# water_system_module.net
KiCad netlist of a schematic drawn in Altium Designer
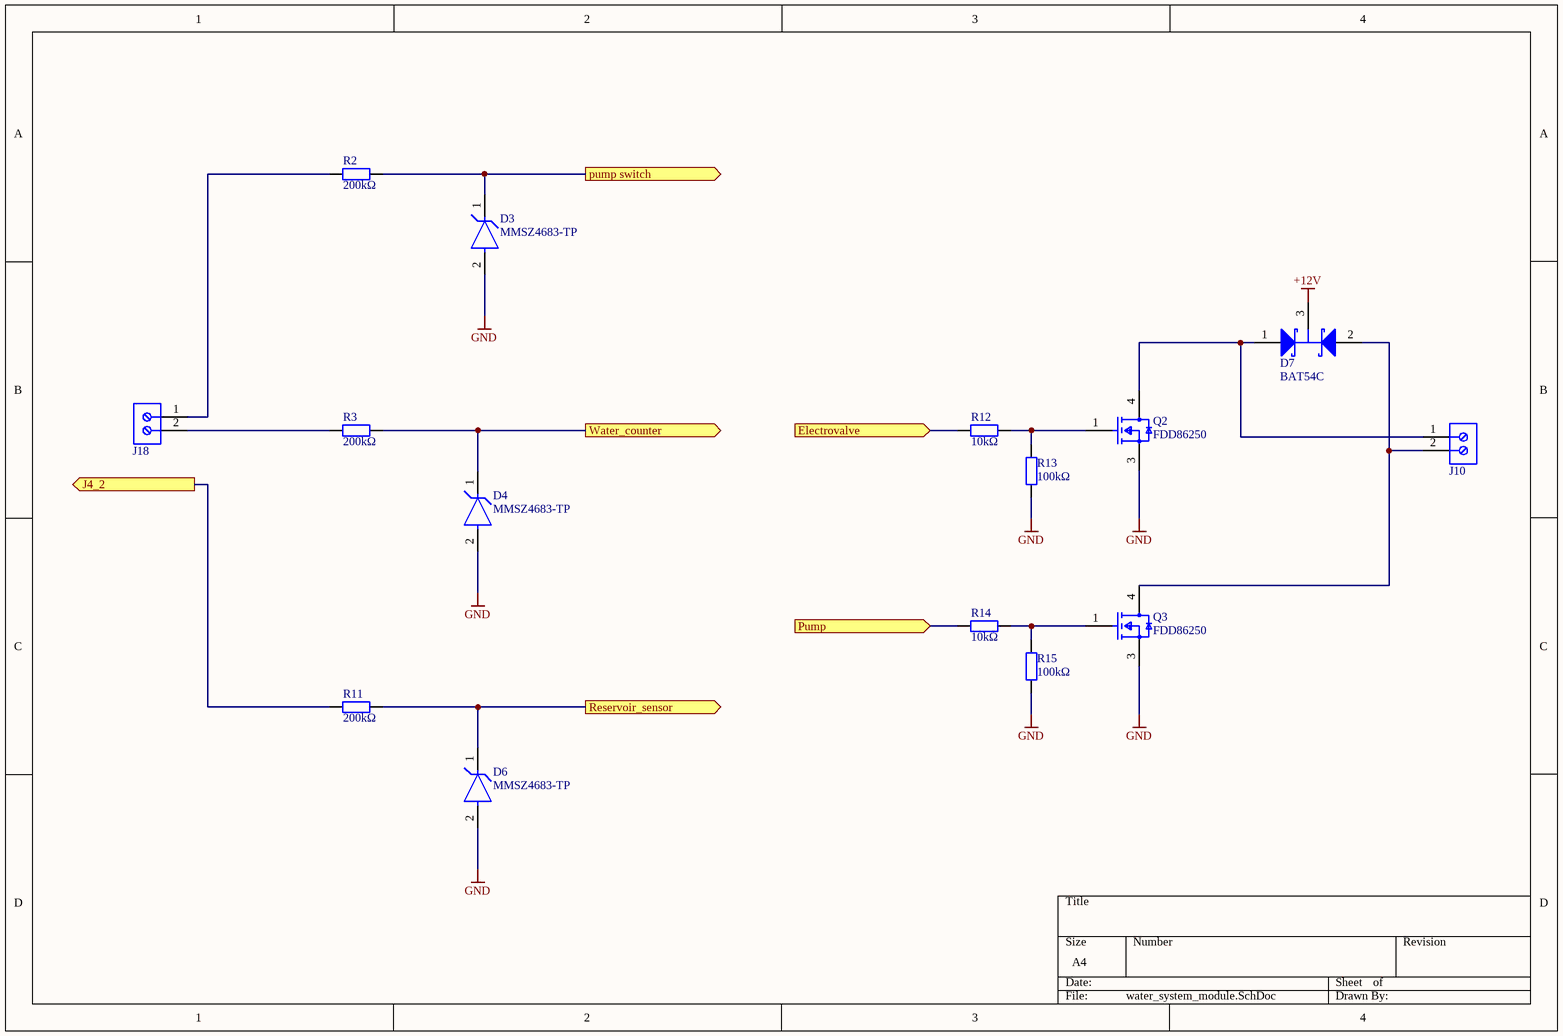
[diagram p0: water_system_module.SchDoc]

(export (version "E")
  (design (tool "Eeschema 10.0.6"))
  (components
    (comp (ref "D3")
      (value "MMSZ4683-TP")
      (footprint "FP-SOD-123-MFG")
      (description "DIODE ZENER 3V 500MW SOD123")
      (fields (field (name "TOLERANCE") "5%"))
      (libsource (lib "Altium Content Vault") (part "f813f71cba58e380607f5dd3caf9714"))
    )
    (comp (ref "D4")
      (value "MMSZ4683-TP")
      (footprint "FP-SOD-123-MFG")
      (description "DIODE ZENER 3V 500MW SOD123")
      (fields (field (name "TOLERANCE") "5%"))
      (libsource (lib "Altium Content Vault") (part "f813f71cba58e380607f5dd3caf9714"))
    )
    (comp (ref "D6")
      (value "MMSZ4683-TP")
      (footprint "FP-SOD-123-MFG")
      (description "DIODE ZENER 3V 500MW SOD123")
      (fields (field (name "TOLERANCE") "5%"))
      (libsource (lib "Altium Content Vault") (part "f813f71cba58e380607f5dd3caf9714"))
    )
    (comp (ref "D7")
      (value "BAT54C")
      (footprint "SOT-23")
      (description "Schottky Barrier Diode, 30 V, 3-Pin SOT23, RoHS, Tape and Reel")
      (fields (field (name "MANUFACTURER") "NXP Semiconductors"))
      (libsource (lib "integrated_library") (part "DIODE_BAT54C"))
    )
    (comp (ref "J10")
      (value "282836-2")
      (footprint "TECO-282836-2_V")
      (description "Female Header, Pitch 5 mm, 1 x 2 Position, Height 10 mm, Tail Length 3.5 mm, Rohs, Bulk")
      (fields (field (name "VOLTAGE") "300V") (field (name "MANUFACTURER") "TE Connectivity"))
      (libsource (lib "Altium Content Vault") (part "CN-1P-F-TB2"))
    )
    (comp (ref "J18")
      (value "282836-2")
      (footprint "TECO-282836-2_V")
      (description "Female Header, Pitch 5 mm, 1 x 2 Position, Height 10 mm, Tail Length 3.5 mm, Rohs, Bulk")
      (fields (field (name "VOLTAGE") "300V") (field (name "MANUFACTURER") "TE Connectivity"))
      (libsource (lib "Altium Content Vault") (part "CN-1P-F-TB2"))
    )
    (comp (ref "Q2")
      (value "FDD86250")
      (footprint "FP-369AS-MFG")
      (description "MOSFET N-CH 150V 8A DPAK")
      (fields
        (field (name "MANUFACTURER") "ON Semiconductor")
        (field (name "OCTOPART") "https://octopart.com/fdd86250-on+semiconductor-84325855")
      )
      (libsource (lib "Altium Content Vault") (part "7ccf16d7e298eaa7d64fcf34af6bb8b"))
    )
    (comp (ref "Q3")
      (value "FDD86250")
      (footprint "FP-369AS-MFG")
      (description "MOSFET N-CH 150V 8A DPAK")
      (fields
        (field (name "MANUFACTURER") "ON Semiconductor")
        (field (name "OCTOPART") "https://octopart.com/fdd86250-on+semiconductor-84325855")
      )
      (libsource (lib "Altium Content Vault") (part "7ccf16d7e298eaa7d64fcf34af6bb8b"))
    )
    (comp (ref "R2")
      (value "200kΩ")
      (footprint "RESC2013X50X30ML20T20")
      (description "Resistor")
      (libsource (lib "PCB_Project") (part "Res_0805"))
    )
    (comp (ref "R3")
      (value "200kΩ")
      (footprint "RESC2013X50X30ML20T20")
      (description "Resistor")
      (libsource (lib "") (part "Res_0805_2"))
    )
    (comp (ref "R11")
      (value "200kΩ")
      (footprint "RESC2013X50X30ML20T20")
      (description "Resistor")
      (libsource (lib "PCB_Project") (part "Res_0805"))
    )
    (comp (ref "R12")
      (value "10kΩ")
      (footprint "RESC2013X50X30ML20T20")
      (description "Resistor")
      (libsource (lib "PCB_Project") (part "Res_0805"))
    )
    (comp (ref "R13")
      (value "100kΩ")
      (footprint "RESC2013X50X30ML20T20")
      (description "Resistor")
      (libsource (lib "") (part "Res_0805_1"))
    )
    (comp (ref "R14")
      (value "10kΩ")
      (footprint "RESC2013X50X30ML20T20")
      (description "Resistor")
      (libsource (lib "PCB_Project") (part "Res_0805"))
    )
    (comp (ref "R15")
      (value "100kΩ")
      (footprint "RESC2013X50X30ML20T20")
      (description "Resistor")
      (libsource (lib "") (part "Res_0805_1"))
    )
  )
  (nets
    (net (code "1") (name "+12V") (class "Default")
      (node (ref "D7") (pin "3") (pinfunction "K_3") (pintype "passive"))
    )
    (net (code "2") (name "/Electrovalve") (class "Default")
      (node (ref "R12") (pin "2") (pinfunction "2_2") (pintype "passive"))
    )
    (net (code "3") (name "/J4_2") (class "Default")
      (node (ref "R11") (pin "2") (pinfunction "2_2") (pintype "passive"))
    )
    (net (code "4") (name "/Pump") (class "Default")
      (node (ref "R14") (pin "2") (pinfunction "2_2") (pintype "passive"))
    )
    (net (code "5") (name "/Reservoir_sensor") (class "Default")
      (node (ref "D6") (pin "1") (pinfunction "C_1") (pintype "passive"))
      (node (ref "R11") (pin "1") (pinfunction "1_1") (pintype "passive"))
    )
    (net (code "6") (name "/Water_counter") (class "Default")
      (node (ref "D4") (pin "1") (pinfunction "C_1") (pintype "passive"))
      (node (ref "R3") (pin "2") (pinfunction "2_2") (pintype "passive"))
    )
    (net (code "7") (name "/pump switch") (class "Default")
      (node (ref "D3") (pin "1") (pinfunction "C_1") (pintype "passive"))
      (node (ref "R2") (pin "1") (pinfunction "1_1") (pintype "passive"))
    )
    (net (code "8") (name "GND") (class "Default")
      (node (ref "D3") (pin "2") (pinfunction "A_2") (pintype "passive"))
      (node (ref "D4") (pin "2") (pinfunction "A_2") (pintype "passive"))
      (node (ref "D6") (pin "2") (pinfunction "A_2") (pintype "passive"))
      (node (ref "Q2") (pin "3") (pinfunction "S_3") (pintype "passive"))
      (node (ref "Q3") (pin "3") (pinfunction "S_3") (pintype "passive"))
      (node (ref "R13") (pin "2") (pinfunction "2_2") (pintype "passive"))
      (node (ref "R15") (pin "2") (pinfunction "2_2") (pintype "passive"))
    )
    (net (code "9") (name "Net-(J18-Pad1)") (class "Default")
      (node (ref "J18") (pin "1") (pinfunction "1_1") (pintype "passive"))
      (node (ref "R2") (pin "2") (pinfunction "2_2") (pintype "passive"))
    )
    (net (code "10") (name "Net-(J18-Pad2)") (class "Default")
      (node (ref "J18") (pin "2") (pinfunction "2_2") (pintype "passive"))
      (node (ref "R3") (pin "1") (pinfunction "1_1") (pintype "passive"))
    )
    (net (code "11") (name "Net-(Q2-D)") (class "Default")
      (node (ref "D7") (pin "1") (pinfunction "A_1") (pintype "passive"))
      (node (ref "J10") (pin "1") (pinfunction "1_1") (pintype "passive"))
      (node (ref "Q2") (pin "4") (pinfunction "D_4") (pintype "passive"))
    )
    (net (code "12") (name "Net-(Q2-G)") (class "Default")
      (node (ref "Q2") (pin "1") (pinfunction "G_1") (pintype "passive"))
      (node (ref "R12") (pin "1") (pinfunction "1_1") (pintype "passive"))
      (node (ref "R13") (pin "1") (pinfunction "1_1") (pintype "passive"))
    )
    (net (code "13") (name "Net-(Q3-D)") (class "Default")
      (node (ref "D7") (pin "2") (pinfunction "A_2") (pintype "passive"))
      (node (ref "J10") (pin "2") (pinfunction "2_2") (pintype "passive"))
      (node (ref "Q3") (pin "4") (pinfunction "D_4") (pintype "passive"))
    )
    (net (code "14") (name "Net-(Q3-G)") (class "Default")
      (node (ref "Q3") (pin "1") (pinfunction "G_1") (pintype "passive"))
      (node (ref "R14") (pin "1") (pinfunction "1_1") (pintype "passive"))
      (node (ref "R15") (pin "1") (pinfunction "1_1") (pintype "passive"))
    )
  )
)
